# BTS.net
KiCad netlist of a schematic drawn in EAGLE
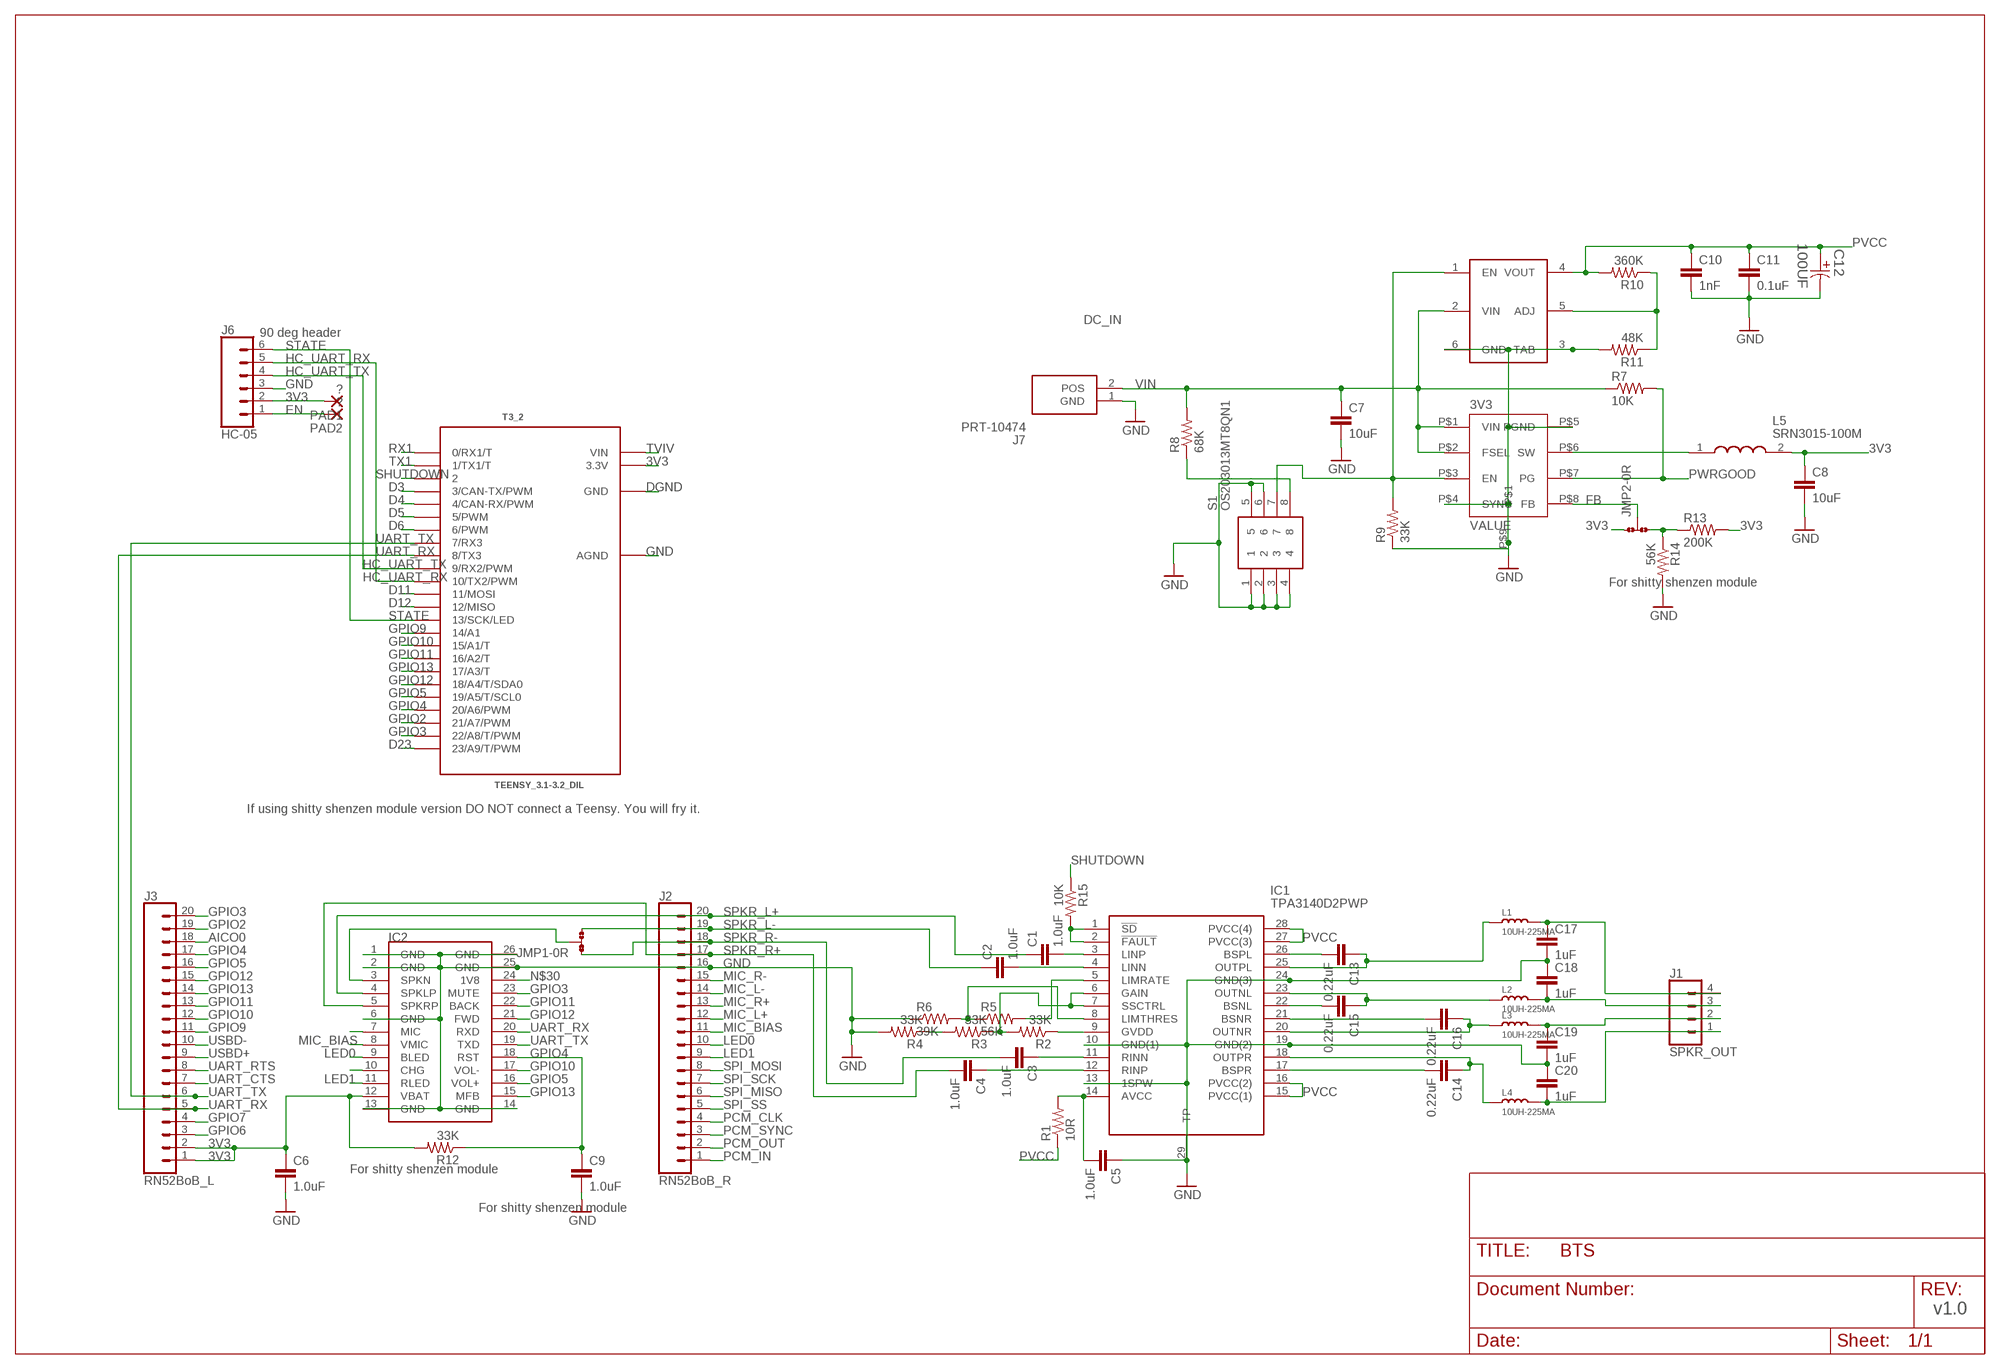
[diagram p0: schematic, sheet 1]

(export (version "E")
  (design (tool "Eeschema 10.0.6"))
  (components
    (comp (ref "3V3")
      (value "ADP2370")
      (footprint "eagle-import:3MM_LFCSP_QFN")
      (libsource (lib "eagle-import") (part "ADP2370"))
    )
    (comp (ref "C1")
      (value "1.0uF")
      (footprint "eagle-import:0603")
      (libsource (lib "eagle-import") (part "1.0UF-0603-16V-10%"))
    )
    (comp (ref "C2")
      (value "1.0uF")
      (footprint "eagle-import:0603")
      (libsource (lib "eagle-import") (part "1.0UF-0603-16V-10%"))
    )
    (comp (ref "C3")
      (value "1.0uF")
      (footprint "eagle-import:0603")
      (libsource (lib "eagle-import") (part "1.0UF-0603-16V-10%"))
    )
    (comp (ref "C4")
      (value "1.0uF")
      (footprint "eagle-import:0603")
      (libsource (lib "eagle-import") (part "1.0UF-0603-16V-10%"))
    )
    (comp (ref "C5")
      (value "1.0uF")
      (footprint "eagle-import:0603")
      (libsource (lib "eagle-import") (part "1.0UF-0603-16V-10%"))
    )
    (comp (ref "C6")
      (value "1.0uF")
      (footprint "eagle-import:0603")
      (libsource (lib "eagle-import") (part "1.0UF-0603-16V-10%"))
    )
    (comp (ref "C7")
      (value "10uF")
      (footprint "eagle-import:C3216")
      (fields (field (name "SPICEPREFIX") "10uF"))
      (libsource (lib "eagle-import") (part "C-EUC3216"))
    )
    (comp (ref "C8")
      (value "10uF")
      (footprint "eagle-import:C3216")
      (libsource (lib "eagle-import") (part "C-EUC3216"))
    )
    (comp (ref "C9")
      (value "1.0uF")
      (footprint "eagle-import:0603")
      (libsource (lib "eagle-import") (part "1.0UF-0603-16V-10%"))
    )
    (comp (ref "C10")
      (value "1nF")
      (footprint "eagle-import:0603")
      (libsource (lib "eagle-import") (part "1.0NF/1000PF-0603-50V-10%"))
    )
    (comp (ref "C11")
      (value "0.1uF")
      (footprint "eagle-import:0603")
      (libsource (lib "eagle-import") (part "0.1UF-0603-25V-(+80/-20%)"))
    )
    (comp (ref "C12")
      (value "100UF")
      (footprint "eagle-import:CAPAE660X610N")
      (fields (field (name "MPN") "EEE-FK1C101P") (field (name "TOLERANCE") "±20 %"))
      (libsource (lib "eagle-import") (part "EEE--CASE-DFK1C101P"))
    )
    (comp (ref "C13")
      (value "0.22uF")
      (footprint "eagle-import:0603")
      (libsource (lib "eagle-import") (part "0.22UF-0603-50V-(-20/+80%)"))
    )
    (comp (ref "C14")
      (value "0.22uF")
      (footprint "eagle-import:0603")
      (libsource (lib "eagle-import") (part "0.22UF-0603-50V-(-20/+80%)"))
    )
    (comp (ref "C15")
      (value "0.22uF")
      (footprint "eagle-import:0603")
      (libsource (lib "eagle-import") (part "0.22UF-0603-50V-(-20/+80%)"))
    )
    (comp (ref "C16")
      (value "0.22uF")
      (footprint "eagle-import:0603")
      (libsource (lib "eagle-import") (part "0.22UF-0603-50V-(-20/+80%)"))
    )
    (comp (ref "C17")
      (value "1uF")
      (footprint "eagle-import:0603")
      (libsource (lib "eagle-import") (part "1.0NF/1000PF-0603-50V-10%"))
    )
    (comp (ref "C18")
      (value "1uF")
      (footprint "eagle-import:0603")
      (libsource (lib "eagle-import") (part "1.0NF/1000PF-0603-50V-10%"))
    )
    (comp (ref "C19")
      (value "1uF")
      (footprint "eagle-import:0603")
      (libsource (lib "eagle-import") (part "1.0NF/1000PF-0603-50V-10%"))
    )
    (comp (ref "C20")
      (value "1uF")
      (footprint "eagle-import:0603")
      (libsource (lib "eagle-import") (part "1.0NF/1000PF-0603-50V-10%"))
    )
    (comp (ref "IC1")
      (value "TPA3140D2PWP")
      (footprint "eagle-import:SOP65P640X120-29N")
      (libsource (lib "eagle-import") (part "TPA3140D2PWP"))
    )
    (comp (ref "IC2")
      (value "BLK-MD-SPK-B")
      (footprint "eagle-import:BLK-MD-SPK-B")
      (libsource (lib "eagle-import") (part "BLK-MD-SPK-B"))
    )
    (comp (ref "J1")
      (value "SPKR_OUT")
      (footprint "eagle-import:SCREWTERMINAL-3.5MM-4")
      (libsource (lib "eagle-import") (part "CONN_04SCREW"))
    )
    (comp (ref "J2")
      (value "RN52BoB_R")
      (footprint "eagle-import:1X20")
      (libsource (lib "eagle-import") (part "CONN_20"))
    )
    (comp (ref "J3")
      (value "RN52BoB_L")
      (footprint "eagle-import:1X20")
      (libsource (lib "eagle-import") (part "CONN_20"))
    )
    (comp (ref "J6")
      (value "HC-05")
      (footprint "eagle-import:1X06")
      (libsource (lib "eagle-import") (part "CONN_06SILK_FEMALE_PTH"))
    )
    (comp (ref "J7")
      (value "PRT-10474")
      (footprint "eagle-import:SHDR2W320P716_1X2_1574X813X158")
      (libsource (lib "eagle-import") (part "PRT-10474"))
    )
    (comp (ref "JMP1")
      (value "0R-JUMPA")
      (footprint "eagle-import:A0R-JMP")
      (libsource (lib "eagle-import") (part "0R-JUMPA"))
    )
    (comp (ref "JMP2")
      (value "0R-JUMPA")
      (footprint "eagle-import:A0R-JMP")
      (libsource (lib "eagle-import") (part "0R-JUMPA"))
    )
    (comp (ref "L1")
      (value "10UH-225MA")
      (footprint "eagle-import:L0806")
      (fields (field (name "MPN") "LQH2MCN100K02L"))
      (libsource (lib "eagle-import") (part "SMD-INDUCTOR-10UH-225MA-10%(0806)"))
    )
    (comp (ref "L2")
      (value "10UH-225MA")
      (footprint "eagle-import:L0806")
      (fields (field (name "MPN") "LQH2MCN100K02L"))
      (libsource (lib "eagle-import") (part "SMD-INDUCTOR-10UH-225MA-10%(0806)"))
    )
    (comp (ref "L3")
      (value "10UH-225MA")
      (footprint "eagle-import:L0806")
      (fields (field (name "MPN") "LQH2MCN100K02L"))
      (libsource (lib "eagle-import") (part "SMD-INDUCTOR-10UH-225MA-10%(0806)"))
    )
    (comp (ref "L4")
      (value "10UH-225MA")
      (footprint "eagle-import:L0806")
      (fields (field (name "MPN") "LQH2MCN100K02L"))
      (libsource (lib "eagle-import") (part "SMD-INDUCTOR-10UH-225MA-10%(0806)"))
    )
    (comp (ref "L5")
      (value "SRN3015-100M")
      (footprint "eagle-import:SRN3015")
      (fields (field (name "RS_PART_NUMBER") "7435071"))
      (libsource (lib "eagle-import") (part "SRN3015-100M"))
    )
    (comp (ref "PAD1")
      (value "?")
      (footprint "eagle-import:SMD1,27-2,54")
      (libsource (lib "eagle-import") (part "SMD2"))
    )
    (comp (ref "PAD2")
      (value "?")
      (footprint "eagle-import:SMD1,27-2,54")
      (libsource (lib "eagle-import") (part "SMD2"))
    )
    (comp (ref "R1")
      (value "10R")
      (footprint "eagle-import:R0603")
      (fields (field (name "RESISTANCE") "10R"))
      (libsource (lib "eagle-import") (part "R-US_R0603"))
    )
    (comp (ref "R2")
      (value "33K")
      (footprint "eagle-import:R0603")
      (fields (field (name "RESISTANCE") "33K"))
      (libsource (lib "eagle-import") (part "R-US_R0603"))
    )
    (comp (ref "R3")
      (value "33K")
      (footprint "eagle-import:R0603")
      (fields (field (name "RESISTANCE") "33K"))
      (libsource (lib "eagle-import") (part "R-US_R0603"))
    )
    (comp (ref "R4")
      (value "33K")
      (footprint "eagle-import:R0603")
      (fields (field (name "RESISTANCE") "33K"))
      (libsource (lib "eagle-import") (part "R-US_R0603"))
    )
    (comp (ref "R5")
      (value "56K")
      (footprint "eagle-import:R0603")
      (fields (field (name "RESISTANCE") "56K"))
      (libsource (lib "eagle-import") (part "R-US_R0603"))
    )
    (comp (ref "R6")
      (value "39K")
      (footprint "eagle-import:R0603")
      (fields (field (name "RESISTANCE") "39K"))
      (libsource (lib "eagle-import") (part "R-US_R0603"))
    )
    (comp (ref "R7")
      (value "10K")
      (footprint "eagle-import:R0603")
      (fields (field (name "RESISTANCE") "10K"))
      (libsource (lib "eagle-import") (part "R-US_R0603"))
    )
    (comp (ref "R8")
      (value "68K")
      (footprint "eagle-import:R0603")
      (fields (field (name "RESISTANCE") "68K"))
      (libsource (lib "eagle-import") (part "R-US_R0603"))
    )
    (comp (ref "R9")
      (value "33K")
      (footprint "eagle-import:R0603")
      (fields (field (name "RESISTANCE") "33K"))
      (libsource (lib "eagle-import") (part "R-US_R0603"))
    )
    (comp (ref "R10")
      (value "360K")
      (footprint "eagle-import:R0603")
      (fields (field (name "RESISTANCE") "10K"))
      (libsource (lib "eagle-import") (part "R-US_R0603"))
    )
    (comp (ref "R11")
      (value "48K")
      (footprint "eagle-import:R0603")
      (fields (field (name "RESISTANCE") "10K"))
      (libsource (lib "eagle-import") (part "R-US_R0603"))
    )
    (comp (ref "R12")
      (value "33K")
      (footprint "eagle-import:R0603")
      (fields (field (name "RESISTANCE") "33K"))
      (libsource (lib "eagle-import") (part "R-US_R0603"))
    )
    (comp (ref "R13")
      (value "200K")
      (footprint "eagle-import:R0603")
      (fields (field (name "RESISTANCE") "10K"))
      (libsource (lib "eagle-import") (part "R-US_R0603"))
    )
    (comp (ref "R14")
      (value "56K")
      (footprint "eagle-import:R0603")
      (fields (field (name "RESISTANCE") "10K"))
      (libsource (lib "eagle-import") (part "R-US_R0603"))
    )
    (comp (ref "R15")
      (value "10K")
      (footprint "eagle-import:R0603")
      (fields (field (name "RESISTANCE") "33K"))
      (libsource (lib "eagle-import") (part "R-US_R0603"))
    )
    (comp (ref "S1")
      (value "OS203013MT8QN1")
      (footprint "eagle-import:OS203013MT8QN1")
      (libsource (lib "eagle-import") (part "OS203013MT8QN1"))
    )
    (comp (ref "T3_2")
      (value "TEENSY_3.1-3.2_DIL")
      (footprint "eagle-import:TEENSY_3.0-3.2&LC_DIL")
      (libsource (lib "eagle-import") (part "TEENSY_3.1-3.2_DIL"))
    )
    (comp (ref "U$2")
      (value "NCP59302")
      (footprint "eagle-import:D2PAK-5")
      (libsource (lib "eagle-import") (part "NCP59302"))
    )
  )
  (nets
    (net (code "1") (name "/3V3") (class "Default")
      (node (ref "C6") (pin "1") (pinfunction "1_1") (pintype "passive"))
      (node (ref "C8") (pin "1") (pinfunction "1_1") (pintype "passive"))
      (node (ref "IC2") (pin "12") (pinfunction "VBAT_12") (pintype "bidirectional"))
      (node (ref "J3") (pin "1") (pinfunction "1_1") (pintype "passive"))
      (node (ref "J3") (pin "2") (pinfunction "2_2") (pintype "passive"))
      (node (ref "J6") (pin "2") (pinfunction "2_2") (pintype "passive"))
      (node (ref "JMP2") (pin "1") (pinfunction "1_1") (pintype "passive"))
      (node (ref "L5") (pin "2") (pinfunction "2_2") (pintype "input"))
      (node (ref "PAD1") (pin "1") (pinfunction "P_1") (pintype "passive"))
      (node (ref "R12") (pin "2") (pinfunction "2_2") (pintype "passive"))
      (node (ref "R13") (pin "2") (pinfunction "2_2") (pintype "passive"))
      (node (ref "T3_2") (pin "3.3V") (pinfunction "3.3V_3.3V") (pintype "power_in"))
    )
    (net (code "2") (name "/AICO0") (class "Default")
      (node (ref "J3") (pin "18") (pinfunction "18_18") (pintype "passive"))
    )
    (net (code "3") (name "/D3") (class "Default")
      (node (ref "T3_2") (pin "3") (pinfunction "3/CAN-TX/PWM_3") (pintype "bidirectional"))
    )
    (net (code "4") (name "/D4") (class "Default")
      (node (ref "T3_2") (pin "4") (pinfunction "4/CAN-RX/PWM_4") (pintype "bidirectional"))
    )
    (net (code "5") (name "/D5") (class "Default")
      (node (ref "T3_2") (pin "5") (pinfunction "5/PWM_5") (pintype "bidirectional"))
    )
    (net (code "6") (name "/D6") (class "Default")
      (node (ref "T3_2") (pin "6") (pinfunction "6/PWM_6") (pintype "bidirectional"))
    )
    (net (code "7") (name "/D11") (class "Default")
      (node (ref "T3_2") (pin "11") (pinfunction "11/MOSI_11") (pintype "bidirectional"))
    )
    (net (code "8") (name "/D12") (class "Default")
      (node (ref "T3_2") (pin "12") (pinfunction "12/MISO_12") (pintype "bidirectional"))
    )
    (net (code "9") (name "/D23") (class "Default")
      (node (ref "T3_2") (pin "23/A9") (pinfunction "23/A9/T/PWM_23/A9") (pintype "bidirectional"))
    )
    (net (code "10") (name "/DGND") (class "Default")
      (node (ref "T3_2") (pin "GND") (pinfunction "GND_GND") (pintype "power_in"))
    )
    (net (code "11") (name "/EN") (class "Default")
      (node (ref "J6") (pin "1") (pinfunction "1_1") (pintype "passive"))
      (node (ref "PAD2") (pin "1") (pinfunction "P_1") (pintype "passive"))
    )
    (net (code "12") (name "/FB") (class "Default")
      (node (ref "3V3") (pin "P$8") (pinfunction "FB_P$8") (pintype "bidirectional"))
      (node (ref "JMP2") (pin "2") (pinfunction "2_2") (pintype "passive"))
    )
    (net (code "13") (name "/GPIO2") (class "Default")
      (node (ref "J3") (pin "19") (pinfunction "19_19") (pintype "passive"))
      (node (ref "T3_2") (pin "21/A7") (pinfunction "21/A7/PWM_21/A7") (pintype "bidirectional"))
    )
    (net (code "14") (name "/GPIO3") (class "Default")
      (node (ref "IC2") (pin "23") (pinfunction "MUTE_23") (pintype "bidirectional"))
      (node (ref "J3") (pin "20") (pinfunction "20_20") (pintype "passive"))
      (node (ref "T3_2") (pin "22/A8") (pinfunction "22/A8/T/PWM_22/A8") (pintype "bidirectional"))
    )
    (net (code "15") (name "/GPIO4") (class "Default")
      (node (ref "C9") (pin "1") (pinfunction "1_1") (pintype "passive"))
      (node (ref "IC2") (pin "18") (pinfunction "RST_18") (pintype "bidirectional"))
      (node (ref "J3") (pin "17") (pinfunction "17_17") (pintype "passive"))
      (node (ref "R12") (pin "1") (pinfunction "1_1") (pintype "passive"))
      (node (ref "T3_2") (pin "20/A6") (pinfunction "20/A6/PWM_20/A6") (pintype "bidirectional"))
    )
    (net (code "16") (name "/GPIO5") (class "Default")
      (node (ref "IC2") (pin "16") (pinfunction "VOL+_16") (pintype "bidirectional"))
      (node (ref "J3") (pin "16") (pinfunction "16_16") (pintype "passive"))
      (node (ref "T3_2") (pin "19/A5") (pinfunction "19/A5/T/SCL0_19/A5") (pintype "bidirectional"))
    )
    (net (code "17") (name "/GPIO6") (class "Default")
      (node (ref "J3") (pin "3") (pinfunction "3_3") (pintype "passive"))
    )
    (net (code "18") (name "/GPIO7") (class "Default")
      (node (ref "J3") (pin "4") (pinfunction "4_4") (pintype "passive"))
    )
    (net (code "19") (name "/GPIO9") (class "Default")
      (node (ref "J3") (pin "11") (pinfunction "11_11") (pintype "passive"))
      (node (ref "T3_2") (pin "14/A0") (pinfunction "14/A1_14/A0") (pintype "bidirectional"))
    )
    (net (code "20") (name "/GPIO10") (class "Default")
      (node (ref "IC2") (pin "17") (pinfunction "VOL-_17") (pintype "bidirectional"))
      (node (ref "J3") (pin "12") (pinfunction "12_12") (pintype "passive"))
      (node (ref "T3_2") (pin "15/A1") (pinfunction "15/A1/T_15/A1") (pintype "bidirectional"))
    )
    (net (code "21") (name "/GPIO11") (class "Default")
      (node (ref "IC2") (pin "22") (pinfunction "BACK_22") (pintype "bidirectional"))
      (node (ref "J3") (pin "13") (pinfunction "13_13") (pintype "passive"))
      (node (ref "T3_2") (pin "16/A2") (pinfunction "16/A2/T_16/A2") (pintype "bidirectional"))
    )
    (net (code "22") (name "/GPIO12") (class "Default")
      (node (ref "IC2") (pin "21") (pinfunction "FWD_21") (pintype "bidirectional"))
      (node (ref "J3") (pin "15") (pinfunction "15_15") (pintype "passive"))
      (node (ref "T3_2") (pin "18/A4") (pinfunction "18/A4/T/SDA0_18/A4") (pintype "bidirectional"))
    )
    (net (code "23") (name "/GPIO13") (class "Default")
      (node (ref "IC2") (pin "15") (pinfunction "MFB_15") (pintype "bidirectional"))
      (node (ref "J3") (pin "14") (pinfunction "14_14") (pintype "passive"))
      (node (ref "T3_2") (pin "17/A3") (pinfunction "17/A3/T_17/A3") (pintype "bidirectional"))
    )
    (net (code "24") (name "/HC_UART_RX") (class "Default")
      (node (ref "J6") (pin "5") (pinfunction "5_5") (pintype "passive"))
      (node (ref "T3_2") (pin "10") (pinfunction "10/TX2/PWM_10") (pintype "bidirectional"))
    )
    (net (code "25") (name "/HC_UART_TX") (class "Default")
      (node (ref "J6") (pin "4") (pinfunction "4_4") (pintype "passive"))
      (node (ref "T3_2") (pin "9") (pinfunction "9/RX2/PWM_9") (pintype "bidirectional"))
    )
    (net (code "26") (name "/LED0") (class "Default")
      (node (ref "IC2") (pin "9") (pinfunction "BLED_9") (pintype "bidirectional"))
      (node (ref "J2") (pin "10") (pinfunction "10_10") (pintype "passive"))
    )
    (net (code "27") (name "/LED1") (class "Default")
      (node (ref "IC2") (pin "11") (pinfunction "RLED_11") (pintype "bidirectional"))
      (node (ref "J2") (pin "9") (pinfunction "9_9") (pintype "passive"))
    )
    (net (code "28") (name "/MIC_BIAS") (class "Default")
      (node (ref "IC2") (pin "8") (pinfunction "VMIC_8") (pintype "bidirectional"))
      (node (ref "J2") (pin "11") (pinfunction "11_11") (pintype "passive"))
    )
    (net (code "29") (name "/MIC_L+") (class "Default")
      (node (ref "J2") (pin "12") (pinfunction "12_12") (pintype "passive"))
    )
    (net (code "30") (name "/MIC_L-") (class "Default")
      (node (ref "J2") (pin "14") (pinfunction "14_14") (pintype "passive"))
    )
    (net (code "31") (name "/MIC_R+") (class "Default")
      (node (ref "J2") (pin "13") (pinfunction "13_13") (pintype "passive"))
    )
    (net (code "32") (name "/MIC_R-") (class "Default")
      (node (ref "J2") (pin "15") (pinfunction "15_15") (pintype "passive"))
    )
    (net (code "33") (name "/N$30") (class "Default")
      (node (ref "IC2") (pin "24") (pinfunction "1V8_24") (pintype "bidirectional"))
    )
    (net (code "34") (name "/PCM_CLK") (class "Default")
      (node (ref "J2") (pin "4") (pinfunction "4_4") (pintype "passive"))
    )
    (net (code "35") (name "/PCM_IN") (class "Default")
      (node (ref "J2") (pin "1") (pinfunction "1_1") (pintype "passive"))
    )
    (net (code "36") (name "/PCM_OUT") (class "Default")
      (node (ref "J2") (pin "2") (pinfunction "2_2") (pintype "passive"))
    )
    (net (code "37") (name "/PCM_SYNC") (class "Default")
      (node (ref "J2") (pin "3") (pinfunction "3_3") (pintype "passive"))
    )
    (net (code "38") (name "/PVCC") (class "Default")
      (node (ref "C10") (pin "1") (pinfunction "1_1") (pintype "passive"))
      (node (ref "C11") (pin "1") (pinfunction "1_1") (pintype "passive"))
      (node (ref "C12") (pin "1") (pinfunction "1_1") (pintype "passive"))
      (node (ref "IC1") (pin "15") (pinfunction "PVCC(1)_15") (pintype "input"))
      (node (ref "IC1") (pin "16") (pinfunction "PVCC(2)_16") (pintype "input"))
      (node (ref "IC1") (pin "27") (pinfunction "PVCC(3)_27") (pintype "input"))
      (node (ref "IC1") (pin "28") (pinfunction "PVCC(4)_28") (pintype "input"))
      (node (ref "R1") (pin "1") (pinfunction "1_1") (pintype "passive"))
      (node (ref "R10") (pin "2") (pinfunction "2_2") (pintype "passive"))
      (node (ref "U$2") (pin "4") (pinfunction "VOUT_4") (pintype "bidirectional"))
    )
    (net (code "39") (name "/PWRGOOD") (class "Default")
      (node (ref "3V3") (pin "P$7") (pinfunction "PG_P$7") (pintype "bidirectional"))
      (node (ref "R7") (pin "2") (pinfunction "2_2") (pintype "passive"))
    )
    (net (code "40") (name "/RX1") (class "Default")
      (node (ref "T3_2") (pin "0") (pinfunction "0/RX1/T_0") (pintype "bidirectional"))
    )
    (net (code "41") (name "/SHUTDOWN") (class "Default")
      (node (ref "R15") (pin "1") (pinfunction "1_1") (pintype "passive"))
      (node (ref "T3_2") (pin "2") (pinfunction "2_2") (pintype "bidirectional"))
    )
    (net (code "42") (name "/SPI_MISO") (class "Default")
      (node (ref "J2") (pin "6") (pinfunction "6_6") (pintype "passive"))
    )
    (net (code "43") (name "/SPI_MOSI") (class "Default")
      (node (ref "J2") (pin "8") (pinfunction "8_8") (pintype "passive"))
    )
    (net (code "44") (name "/SPI_SCK") (class "Default")
      (node (ref "J2") (pin "7") (pinfunction "7_7") (pintype "passive"))
    )
    (net (code "45") (name "/SPI_SS") (class "Default")
      (node (ref "J2") (pin "5") (pinfunction "5_5") (pintype "passive"))
    )
    (net (code "46") (name "/SPKR_L+") (class "Default")
      (node (ref "C1") (pin "1") (pinfunction "1_1") (pintype "passive"))
      (node (ref "IC2") (pin "4") (pinfunction "SPKLP_4") (pintype "bidirectional"))
      (node (ref "J2") (pin "20") (pinfunction "20_20") (pintype "passive"))
    )
    (net (code "47") (name "/SPKR_L-") (class "Default")
      (node (ref "C2") (pin "1") (pinfunction "1_1") (pintype "passive"))
      (node (ref "J2") (pin "19") (pinfunction "19_19") (pintype "passive"))
      (node (ref "JMP1") (pin "3") (pinfunction "3_3") (pintype "passive"))
    )
    (net (code "48") (name "/SPKR_R+") (class "Default")
      (node (ref "C4") (pin "2") (pinfunction "2_2") (pintype "passive"))
      (node (ref "IC2") (pin "5") (pinfunction "SPKRP_5") (pintype "bidirectional"))
      (node (ref "J2") (pin "17") (pinfunction "17_17") (pintype "passive"))
    )
    (net (code "49") (name "/SPKR_R-") (class "Default")
      (node (ref "C3") (pin "2") (pinfunction "2_2") (pintype "passive"))
      (node (ref "J2") (pin "18") (pinfunction "18_18") (pintype "passive"))
      (node (ref "JMP1") (pin "1") (pinfunction "1_1") (pintype "passive"))
    )
    (net (code "50") (name "/STATE") (class "Default")
      (node (ref "J6") (pin "6") (pinfunction "6_6") (pintype "passive"))
      (node (ref "T3_2") (pin "13") (pinfunction "13/SCK/LED_13") (pintype "bidirectional"))
    )
    (net (code "51") (name "/TVIV") (class "Default")
      (node (ref "T3_2") (pin "VIN") (pinfunction "VIN_VIN") (pintype "power_in"))
    )
    (net (code "52") (name "/TX1") (class "Default")
      (node (ref "T3_2") (pin "1") (pinfunction "1/TX1/T_1") (pintype "bidirectional"))
    )
    (net (code "53") (name "/UART_CTS") (class "Default")
      (node (ref "J3") (pin "7") (pinfunction "7_7") (pintype "passive"))
    )
    (net (code "54") (name "/UART_RTS") (class "Default")
      (node (ref "J3") (pin "8") (pinfunction "8_8") (pintype "passive"))
    )
    (net (code "55") (name "/UART_RX") (class "Default")
      (node (ref "IC2") (pin "20") (pinfunction "RXD_20") (pintype "bidirectional"))
      (node (ref "J3") (pin "5") (pinfunction "5_5") (pintype "passive"))
      (node (ref "T3_2") (pin "8") (pinfunction "8/TX3_8") (pintype "bidirectional"))
    )
    (net (code "56") (name "/UART_TX") (class "Default")
      (node (ref "IC2") (pin "19") (pinfunction "TXD_19") (pintype "bidirectional"))
      (node (ref "J3") (pin "6") (pinfunction "6_6") (pintype "passive"))
      (node (ref "T3_2") (pin "7") (pinfunction "7/RX3_7") (pintype "bidirectional"))
    )
    (net (code "57") (name "/USBD+") (class "Default")
      (node (ref "J3") (pin "9") (pinfunction "9_9") (pintype "passive"))
    )
    (net (code "58") (name "/USBD-") (class "Default")
      (node (ref "J3") (pin "10") (pinfunction "10_10") (pintype "passive"))
    )
    (net (code "59") (name "/VIN") (class "Default")
      (node (ref "3V3") (pin "P$1") (pinfunction "VIN_P$1") (pintype "bidirectional"))
      (node (ref "3V3") (pin "P$2") (pinfunction "FSEL_P$2") (pintype "bidirectional"))
      (node (ref "C7") (pin "1") (pinfunction "1_1") (pintype "passive"))
      (node (ref "J7") (pin "2") (pinfunction "POS_2") (pintype "input"))
      (node (ref "R7") (pin "1") (pinfunction "1_1") (pintype "passive"))
      (node (ref "R8") (pin "2") (pinfunction "2_2") (pintype "passive"))
      (node (ref "U$2") (pin "2") (pinfunction "VIN_2") (pintype "bidirectional"))
    )
    (net (code "60") (name "GND") (class "Default")
      (node (ref "3V3") (pin "P$4") (pinfunction "SYNC_P$4") (pintype "bidirectional"))
      (node (ref "3V3") (pin "P$5") (pinfunction "PGND_P$5") (pintype "bidirectional"))
      (node (ref "3V3") (pin "P$9") (pinfunction "P$1_P$9") (pintype "bidirectional"))
      (node (ref "C10") (pin "2") (pinfunction "2_2") (pintype "passive"))
      (node (ref "C11") (pin "2") (pinfunction "2_2") (pintype "passive"))
      (node (ref "C12") (pin "2") (pinfunction "2_2") (pintype "passive"))
      (node (ref "C17") (pin "2") (pinfunction "2_2") (pintype "passive"))
      (node (ref "C18") (pin "1") (pinfunction "1_1") (pintype "passive"))
      (node (ref "C19") (pin "2") (pinfunction "2_2") (pintype "passive"))
      (node (ref "C20") (pin "1") (pinfunction "1_1") (pintype "passive"))
      (node (ref "C5") (pin "1") (pinfunction "1_1") (pintype "passive"))
      (node (ref "C6") (pin "2") (pinfunction "2_2") (pintype "passive"))
      (node (ref "C7") (pin "2") (pinfunction "2_2") (pintype "passive"))
      (node (ref "C8") (pin "2") (pinfunction "2_2") (pintype "passive"))
      (node (ref "C9") (pin "2") (pinfunction "2_2") (pintype "passive"))
      (node (ref "IC1") (pin "10") (pinfunction "GND(1)_10") (pintype "input"))
      (node (ref "IC1") (pin "13") (pinfunction "1SPW_13") (pintype "input"))
      (node (ref "IC1") (pin "19") (pinfunction "GND(2)_19") (pintype "input"))
      (node (ref "IC1") (pin "24") (pinfunction "GND(3)_24") (pintype "input"))
      (node (ref "IC1") (pin "29") (pinfunction "TP_29") (pintype "input"))
      (node (ref "IC2") (pin "1") (pinfunction "GND_1") (pintype "bidirectional"))
      (node (ref "IC2") (pin "13") (pinfunction "GND_13") (pintype "bidirectional"))
      (node (ref "IC2") (pin "14") (pinfunction "GND_14") (pintype "bidirectional"))
      (node (ref "IC2") (pin "2") (pinfunction "GND_2") (pintype "bidirectional"))
      (node (ref "IC2") (pin "25") (pinfunction "GND_25") (pintype "bidirectional"))
      (node (ref "IC2") (pin "26") (pinfunction "GND_26") (pintype "bidirectional"))
      (node (ref "IC2") (pin "6") (pinfunction "GND_6") (pintype "bidirectional"))
      (node (ref "J2") (pin "16") (pinfunction "16_16") (pintype "passive"))
      (node (ref "J6") (pin "3") (pinfunction "3_3") (pintype "passive"))
      (node (ref "J7") (pin "1") (pinfunction "GND_1") (pintype "input"))
      (node (ref "R11") (pin "2") (pinfunction "2_2") (pintype "passive"))
      (node (ref "R14") (pin "2") (pinfunction "2_2") (pintype "passive"))
      (node (ref "R4") (pin "2") (pinfunction "2_2") (pintype "passive"))
      (node (ref "R6") (pin "1") (pinfunction "1_1") (pintype "passive"))
      (node (ref "R9") (pin "1") (pinfunction "1_1") (pintype "passive"))
      (node (ref "S1") (pin "1") (pinfunction "1_1") (pintype "input"))
      (node (ref "S1") (pin "2") (pinfunction "2_2") (pintype "input"))
      (node (ref "S1") (pin "3") (pinfunction "3_3") (pintype "input"))
      (node (ref "S1") (pin "4") (pinfunction "4_4") (pintype "input"))
      (node (ref "S1") (pin "5") (pinfunction "5_5") (pintype "input"))
      (node (ref "S1") (pin "6") (pinfunction "6_6") (pintype "input"))
      (node (ref "T3_2") (pin "AGND") (pinfunction "AGND_AGND") (pintype "power_in"))
      (node (ref "U$2") (pin "3") (pinfunction "TAB_3") (pintype "bidirectional"))
      (node (ref "U$2") (pin "6") (pinfunction "GND_6") (pintype "bidirectional"))
    )
    (net (code "61") (name "Net-(3V3-EN)") (class "Default")
      (node (ref "3V3") (pin "P$3") (pinfunction "EN_P$3") (pintype "bidirectional"))
      (node (ref "R9") (pin "2") (pinfunction "2_2") (pintype "passive"))
      (node (ref "S1") (pin "7") (pinfunction "7_7") (pintype "input"))
      (node (ref "U$2") (pin "1") (pinfunction "EN_1") (pintype "bidirectional"))
    )
    (net (code "62") (name "Net-(3V3-SW)") (class "Default")
      (node (ref "3V3") (pin "P$6") (pinfunction "SW_P$6") (pintype "bidirectional"))
      (node (ref "L5") (pin "1") (pinfunction "1_1") (pintype "input"))
    )
    (net (code "63") (name "Net-(C17-Pad1)") (class "Default")
      (node (ref "C17") (pin "1") (pinfunction "1_1") (pintype "passive"))
      (node (ref "J1") (pin "4") (pinfunction "4_4") (pintype "passive"))
      (node (ref "L1") (pin "2") (pinfunction "2_2") (pintype "passive"))
    )
    (net (code "64") (name "Net-(C18-Pad2)") (class "Default")
      (node (ref "C18") (pin "2") (pinfunction "2_2") (pintype "passive"))
      (node (ref "J1") (pin "3") (pinfunction "3_3") (pintype "passive"))
      (node (ref "L2") (pin "2") (pinfunction "2_2") (pintype "passive"))
    )
    (net (code "65") (name "Net-(C19-Pad1)") (class "Default")
      (node (ref "C19") (pin "1") (pinfunction "1_1") (pintype "passive"))
      (node (ref "J1") (pin "2") (pinfunction "2_2") (pintype "passive"))
      (node (ref "L3") (pin "2") (pinfunction "2_2") (pintype "passive"))
    )
    (net (code "66") (name "Net-(C20-Pad2)") (class "Default")
      (node (ref "C20") (pin "2") (pinfunction "2_2") (pintype "passive"))
      (node (ref "J1") (pin "1") (pinfunction "1_1") (pintype "passive"))
      (node (ref "L4") (pin "2") (pinfunction "2_2") (pintype "passive"))
    )
    (net (code "67") (name "Net-(IC1-AVCC)") (class "Default")
      (node (ref "C5") (pin "2") (pinfunction "2_2") (pintype "passive"))
      (node (ref "IC1") (pin "14") (pinfunction "AVCC_14") (pintype "input"))
      (node (ref "R1") (pin "2") (pinfunction "2_2") (pintype "passive"))
    )
    (net (code "68") (name "Net-(IC1-BSNL)") (class "Default")
      (node (ref "C15") (pin "2") (pinfunction "2_2") (pintype "passive"))
      (node (ref "IC1") (pin "22") (pinfunction "BSNL_22") (pintype "input"))
    )
    (net (code "69") (name "Net-(IC1-BSNR)") (class "Default")
      (node (ref "C16") (pin "2") (pinfunction "2_2") (pintype "passive"))
      (node (ref "IC1") (pin "21") (pinfunction "BSNR_21") (pintype "input"))
    )
    (net (code "70") (name "Net-(IC1-BSPL)") (class "Default")
      (node (ref "C13") (pin "2") (pinfunction "2_2") (pintype "passive"))
      (node (ref "IC1") (pin "26") (pinfunction "BSPL_26") (pintype "input"))
    )
    (net (code "71") (name "Net-(IC1-BSPR)") (class "Default")
      (node (ref "C14") (pin "2") (pinfunction "2_2") (pintype "passive"))
      (node (ref "IC1") (pin "17") (pinfunction "BSPR_17") (pintype "input"))
    )
    (net (code "72") (name "Net-(IC1-GAIN)") (class "Default")
      (node (ref "IC1") (pin "6") (pinfunction "GAIN_6") (pintype "input"))
      (node (ref "IC1") (pin "7") (pinfunction "SSCTRL_7") (pintype "input"))
      (node (ref "R2") (pin "2") (pinfunction "2_2") (pintype "passive"))
      (node (ref "R3") (pin "1") (pinfunction "1_1") (pintype "passive"))
    )
    (net (code "73") (name "Net-(IC1-GVDD)") (class "Default")
      (node (ref "IC1") (pin "9") (pinfunction "GVDD_9") (pintype "input"))
      (node (ref "R2") (pin "1") (pinfunction "1_1") (pintype "passive"))
    )
    (net (code "74") (name "Net-(IC1-LIMRATE)") (class "Default")
      (node (ref "IC1") (pin "5") (pinfunction "LIMRATE_5") (pintype "input"))
      (node (ref "R5") (pin "2") (pinfunction "2_2") (pintype "passive"))
    )
    (net (code "75") (name "Net-(IC1-LIMTHRES)") (class "Default")
      (node (ref "IC1") (pin "8") (pinfunction "LIMTHRES_8") (pintype "input"))
      (node (ref "R5") (pin "1") (pinfunction "1_1") (pintype "passive"))
      (node (ref "R6") (pin "2") (pinfunction "2_2") (pintype "passive"))
    )
    (net (code "76") (name "Net-(IC1-LINN)") (class "Default")
      (node (ref "C2") (pin "2") (pinfunction "2_2") (pintype "passive"))
      (node (ref "IC1") (pin "4") (pinfunction "LINN_4") (pintype "input"))
    )
    (net (code "77") (name "Net-(IC1-LINP)") (class "Default")
      (node (ref "C1") (pin "2") (pinfunction "2_2") (pintype "passive"))
      (node (ref "IC1") (pin "3") (pinfunction "LINP_3") (pintype "input"))
    )
    (net (code "78") (name "Net-(IC1-OUTNL)") (class "Default")
      (node (ref "C15") (pin "1") (pinfunction "1_1") (pintype "passive"))
      (node (ref "IC1") (pin "23") (pinfunction "OUTNL_23") (pintype "input"))
      (node (ref "L2") (pin "1") (pinfunction "1_1") (pintype "passive"))
    )
    (net (code "79") (name "Net-(IC1-OUTNR)") (class "Default")
      (node (ref "C16") (pin "1") (pinfunction "1_1") (pintype "passive"))
      (node (ref "IC1") (pin "20") (pinfunction "OUTNR_20") (pintype "input"))
      (node (ref "L3") (pin "1") (pinfunction "1_1") (pintype "passive"))
    )
    (net (code "80") (name "Net-(IC1-OUTPL)") (class "Default")
      (node (ref "C13") (pin "1") (pinfunction "1_1") (pintype "passive"))
      (node (ref "IC1") (pin "25") (pinfunction "OUTPL_25") (pintype "input"))
      (node (ref "L1") (pin "1") (pinfunction "1_1") (pintype "passive"))
    )
    (net (code "81") (name "Net-(IC1-OUTPR)") (class "Default")
      (node (ref "C14") (pin "1") (pinfunction "1_1") (pintype "passive"))
      (node (ref "IC1") (pin "18") (pinfunction "OUTPR_18") (pintype "input"))
      (node (ref "L4") (pin "1") (pinfunction "1_1") (pintype "passive"))
    )
    (net (code "82") (name "Net-(IC1-RINN)") (class "Default")
      (node (ref "C3") (pin "1") (pinfunction "1_1") (pintype "passive"))
      (node (ref "IC1") (pin "11") (pinfunction "RINN_11") (pintype "input"))
    )
    (net (code "83") (name "Net-(IC1-RINP)") (class "Default")
      (node (ref "C4") (pin "1") (pinfunction "1_1") (pintype "passive"))
      (node (ref "IC1") (pin "12") (pinfunction "RINP_12") (pintype "input"))
    )
    (net (code "84") (name "Net-(IC1-~{FAULT})") (class "Default")
      (node (ref "IC1") (pin "1") (pinfunction "~{SD}_1") (pintype "input"))
      (node (ref "IC1") (pin "2") (pinfunction "~{FAULT}_2") (pintype "input"))
      (node (ref "R15") (pin "2") (pinfunction "2_2") (pintype "passive"))
    )
    (net (code "85") (name "Net-(IC2-SPKN)") (class "Default")
      (node (ref "IC2") (pin "3") (pinfunction "SPKN_3") (pintype "bidirectional"))
      (node (ref "JMP1") (pin "2") (pinfunction "2_2") (pintype "passive"))
    )
    (net (code "86") (name "Net-(JMP2-Pad3)") (class "Default")
      (node (ref "JMP2") (pin "3") (pinfunction "3_3") (pintype "passive"))
      (node (ref "R13") (pin "1") (pinfunction "1_1") (pintype "passive"))
      (node (ref "R14") (pin "1") (pinfunction "1_1") (pintype "passive"))
    )
    (net (code "87") (name "Net-(R3-Pad2)") (class "Default")
      (node (ref "R3") (pin "2") (pinfunction "2_2") (pintype "passive"))
      (node (ref "R4") (pin "1") (pinfunction "1_1") (pintype "passive"))
    )
    (net (code "88") (name "Net-(R8-Pad1)") (class "Default")
      (node (ref "R8") (pin "1") (pinfunction "1_1") (pintype "passive"))
      (node (ref "S1") (pin "8") (pinfunction "8_8") (pintype "input"))
    )
    (net (code "89") (name "Net-(U$2-ADJ)") (class "Default")
      (node (ref "R10") (pin "1") (pinfunction "1_1") (pintype "passive"))
      (node (ref "R11") (pin "1") (pinfunction "1_1") (pintype "passive"))
      (node (ref "U$2") (pin "5") (pinfunction "ADJ_5") (pintype "bidirectional"))
    )
    (net (code "90") (name "unconnected-(IC2-CHG-Pad10)") (class "Default")
      (node (ref "IC2") (pin "10") (pinfunction "CHG_10") (pintype "bidirectional"))
    )
    (net (code "91") (name "unconnected-(IC2-MIC-Pad7)") (class "Default")
      (node (ref "IC2") (pin "7") (pinfunction "MIC_7") (pintype "bidirectional"))
    )
  )
)
